# pico.net
KiCad netlist of a schematic drawn in EAGLE
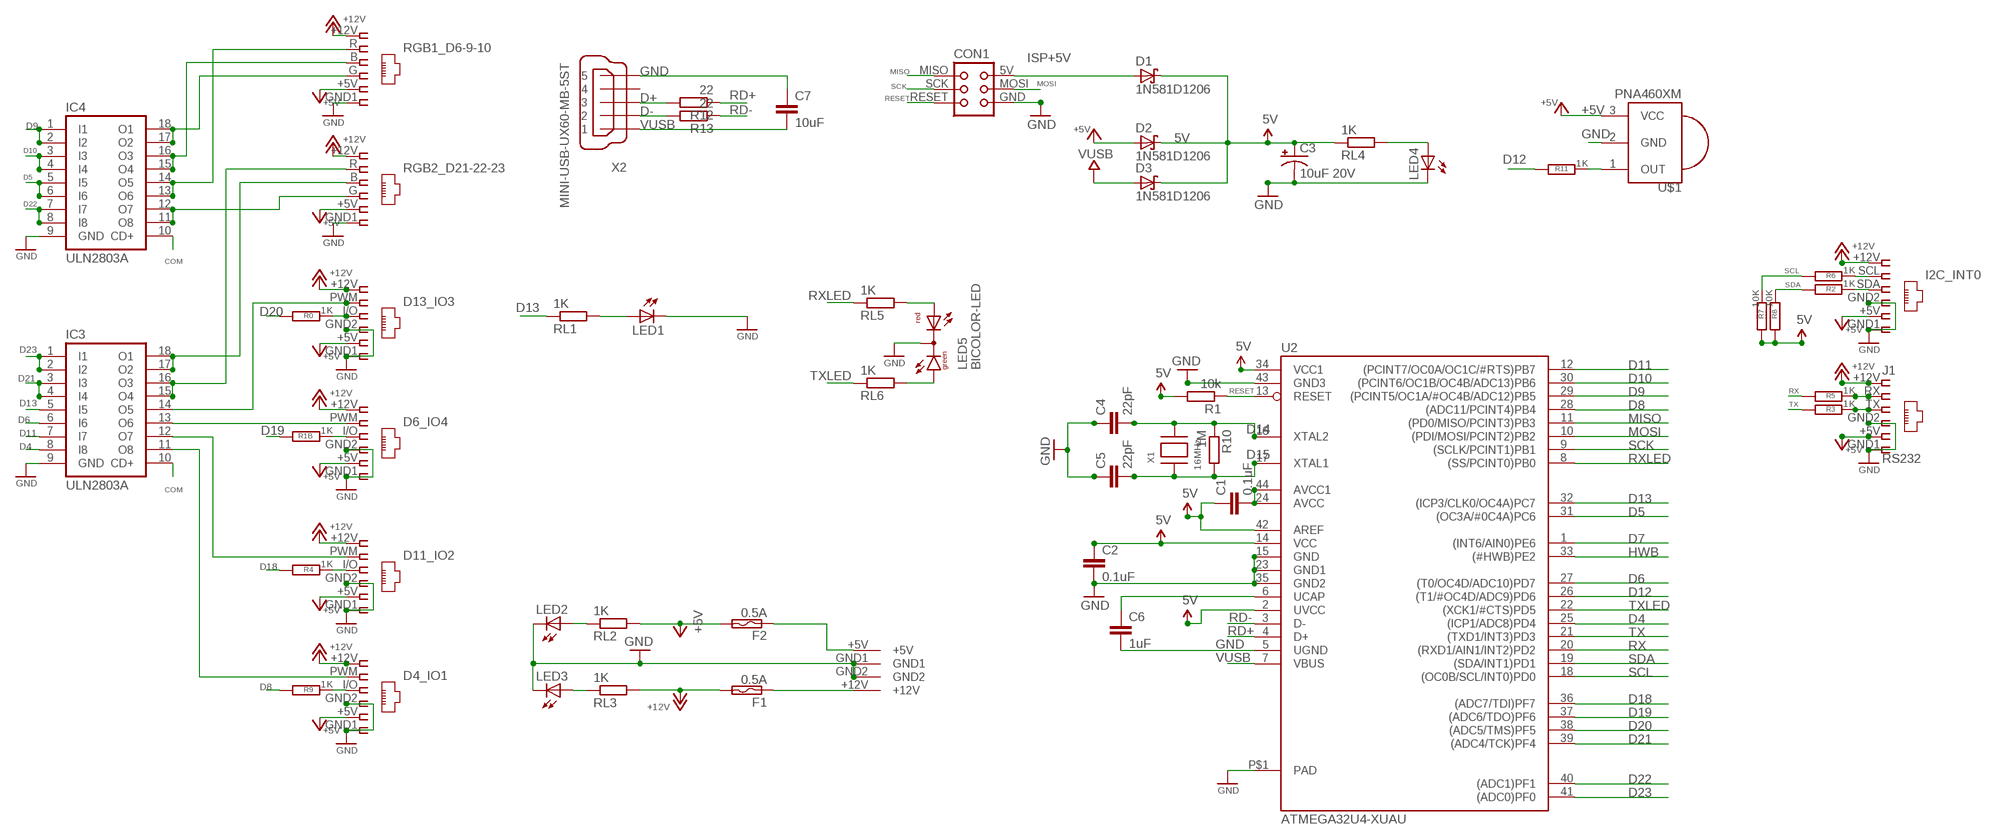
[diagram p0: schematic, sheet 1]

(export (version "E")
  (design (tool "Eeschema 10.0.6"))
  (components
    (comp (ref "C1")
      (value "0.1uF")
      (footprint "eagle-import:C1206")
      (libsource (lib "eagle-import") (part "C-EUC1206"))
    )
    (comp (ref "C2")
      (value "0.1uF")
      (footprint "eagle-import:C1206")
      (libsource (lib "eagle-import") (part "C-EUC1206"))
    )
    (comp (ref "C3")
      (value "10uF 20V")
      (footprint "eagle-import:EIA3216-KIT")
      (libsource (lib "eagle-import") (part "CAP_POL1206-KIT"))
    )
    (comp (ref "C4")
      (value "22pF")
      (footprint "eagle-import:C1206")
      (libsource (lib "eagle-import") (part "C-EUC1206"))
    )
    (comp (ref "C5")
      (value "22pF")
      (footprint "eagle-import:C1206")
      (libsource (lib "eagle-import") (part "C-EUC1206"))
    )
    (comp (ref "C6")
      (value "1uF")
      (footprint "eagle-import:C1206")
      (libsource (lib "eagle-import") (part "C-EUC1206"))
    )
    (comp (ref "C7")
      (value "10uF")
      (footprint "eagle-import:C1206")
      (libsource (lib "eagle-import") (part "C-EUC1206"))
    )
    (comp (ref "CON1")
      (value "TINYISPT")
      (footprint "eagle-import:TC2030-MCP-NL")
      (libsource (lib "eagle-import") (part "TINYISPT"))
    )
    (comp (ref "D1")
      (value "1N581D1206")
      (footprint "eagle-import:LED-1206")
      (libsource (lib "eagle-import") (part "1N581D1206"))
    )
    (comp (ref "D2")
      (value "1N581D1206")
      (footprint "eagle-import:LED-1206")
      (libsource (lib "eagle-import") (part "1N581D1206"))
    )
    (comp (ref "D3")
      (value "1N581D1206")
      (footprint "eagle-import:LED-1206")
      (libsource (lib "eagle-import") (part "1N581D1206"))
    )
    (comp (ref "D4_IO1")
      (value "IO1")
      (footprint "eagle-import:RJ12-STRAIGHT")
      (libsource (lib "eagle-import") (part "RJ12STRAIGHT"))
    )
    (comp (ref "D6_IO4")
      (value "IO3")
      (footprint "eagle-import:RJ12-STRAIGHT")
      (libsource (lib "eagle-import") (part "RJ12STRAIGHT"))
    )
    (comp (ref "D11_IO2")
      (value "IO2")
      (footprint "eagle-import:RJ12-STRAIGHT")
      (libsource (lib "eagle-import") (part "RJ12STRAIGHT"))
    )
    (comp (ref "D13_IO3")
      (value "IO4")
      (footprint "eagle-import:RJ12-STRAIGHT")
      (libsource (lib "eagle-import") (part "RJ12STRAIGHT"))
    )
    (comp (ref "F1")
      (value "0.5A")
      (footprint "eagle-import:C1812")
      (libsource (lib "eagle-import") (part "POLYSWITCHSMD1812"))
    )
    (comp (ref "F2")
      (value "0.5A")
      (footprint "eagle-import:C1812")
      (libsource (lib "eagle-import") (part "POLYSWITCHSMD1812"))
    )
    (comp (ref "I2C_INT0")
      (value "I2C")
      (footprint "eagle-import:RJ12-STRAIGHT-I2C")
      (libsource (lib "eagle-import") (part "RJ12STRAIGHT-I2C"))
    )
    (comp (ref "IC3")
      (value "ULN2803A")
      (footprint "eagle-import:SO18W")
      (libsource (lib "eagle-import") (part "ULN2803A"))
    )
    (comp (ref "IC4")
      (value "ULN2803A")
      (footprint "eagle-import:SO18W")
      (libsource (lib "eagle-import") (part "ULN2803A"))
    )
    (comp (ref "J1")
      (value "RS232")
      (footprint "eagle-import:RJ12-STRAIGHT-RS232")
      (libsource (lib "eagle-import") (part "RJ12STRAIGHT-RS232-SERVER"))
    )
    (comp (ref "LED1")
      (value "LED3MM")
      (footprint "eagle-import:LED3MM")
      (libsource (lib "eagle-import") (part "LED3MM"))
    )
    (comp (ref "LED2")
      (value "5V")
      (footprint "eagle-import:LED3MM")
      (libsource (lib "eagle-import") (part "LED3MM"))
    )
    (comp (ref "LED3")
      (value "12V")
      (footprint "eagle-import:LED3MM")
      (libsource (lib "eagle-import") (part "LED3MM"))
    )
    (comp (ref "LED4")
      (value "5V uC")
      (footprint "eagle-import:LED3MM")
      (libsource (lib "eagle-import") (part "LED3MM"))
    )
    (comp (ref "LED5")
      (value "BICOLOR-LED")
      (footprint "eagle-import:BICOLOR-3MM")
      (libsource (lib "eagle-import") (part "BICOLOR-LED"))
    )
    (comp (ref "R0")
      (value "1K")
      (footprint "eagle-import:M1206")
      (libsource (lib "eagle-import") (part "R-EU_M1206"))
    )
    (comp (ref "R1")
      (value "10k")
      (footprint "eagle-import:M1206")
      (libsource (lib "eagle-import") (part "R-EU_M1206"))
    )
    (comp (ref "R1B")
      (value "1K")
      (footprint "eagle-import:M1206")
      (libsource (lib "eagle-import") (part "R-EU_M1206"))
    )
    (comp (ref "R2")
      (value "1K")
      (footprint "eagle-import:M1206")
      (libsource (lib "eagle-import") (part "R-EU_M1206"))
    )
    (comp (ref "R3")
      (value "1K")
      (footprint "eagle-import:M1206")
      (libsource (lib "eagle-import") (part "R-EU_M1206"))
    )
    (comp (ref "R4")
      (value "1K")
      (footprint "eagle-import:M1206")
      (libsource (lib "eagle-import") (part "R-EU_M1206"))
    )
    (comp (ref "R5")
      (value "1K")
      (footprint "eagle-import:M1206")
      (libsource (lib "eagle-import") (part "R-EU_M1206"))
    )
    (comp (ref "R6")
      (value "1K")
      (footprint "eagle-import:M1206")
      (libsource (lib "eagle-import") (part "R-EU_M1206"))
    )
    (comp (ref "R7")
      (value "10K")
      (footprint "eagle-import:M1206")
      (libsource (lib "eagle-import") (part "R-EU_M1206"))
    )
    (comp (ref "R8")
      (value "10K")
      (footprint "eagle-import:M1206")
      (libsource (lib "eagle-import") (part "R-EU_M1206"))
    )
    (comp (ref "R9")
      (value "1K")
      (footprint "eagle-import:M1206")
      (libsource (lib "eagle-import") (part "R-EU_M1206"))
    )
    (comp (ref "R10")
      (value "1M")
      (footprint "eagle-import:M1206")
      (libsource (lib "eagle-import") (part "R-EU_M1206"))
    )
    (comp (ref "R11")
      (value "1K")
      (footprint "eagle-import:M1206")
      (libsource (lib "eagle-import") (part "R-EU_M1206"))
    )
    (comp (ref "R12")
      (value "22")
      (footprint "eagle-import:M1206")
      (libsource (lib "eagle-import") (part "R-EU_M1206"))
    )
    (comp (ref "R13")
      (value "22")
      (footprint "eagle-import:M1206")
      (libsource (lib "eagle-import") (part "R-EU_M1206"))
    )
    (comp (ref "RGB1_D6-9-10")
      (value "RGB1")
      (footprint "eagle-import:RJ12-STRAIGHT-RGB")
      (libsource (lib "eagle-import") (part "RJ12STRAIGHT-RGB"))
    )
    (comp (ref "RGB2_D21-22-23")
      (value "RGB2")
      (footprint "eagle-import:RJ12-STRAIGHT-RGB")
      (libsource (lib "eagle-import") (part "RJ12STRAIGHT-RGB"))
    )
    (comp (ref "RL1")
      (value "1K")
      (footprint "eagle-import:M1206")
      (libsource (lib "eagle-import") (part "R-EU_M1206"))
    )
    (comp (ref "RL2")
      (value "1K")
      (footprint "eagle-import:M1206")
      (libsource (lib "eagle-import") (part "R-EU_M1206"))
    )
    (comp (ref "RL3")
      (value "1K")
      (footprint "eagle-import:M1206")
      (libsource (lib "eagle-import") (part "R-EU_M1206"))
    )
    (comp (ref "RL4")
      (value "1K")
      (footprint "eagle-import:M1206")
      (libsource (lib "eagle-import") (part "R-EU_M1206"))
    )
    (comp (ref "RL5")
      (value "1K")
      (footprint "eagle-import:M1206")
      (libsource (lib "eagle-import") (part "R-EU_M1206"))
    )
    (comp (ref "RL6")
      (value "1K")
      (footprint "eagle-import:M1206")
      (libsource (lib "eagle-import") (part "R-EU_M1206"))
    )
    (comp (ref "U$1")
      (value "PNA460XM")
      (footprint "eagle-import:PNA460XM")
      (libsource (lib "eagle-import") (part "PNA460XM"))
    )
    (comp (ref "U$2")
      (value "KPJX-4S-S")
      (footprint "eagle-import:KPJX-4S-S")
      (libsource (lib "eagle-import") (part "KPJX-4S-S"))
    )
    (comp (ref "U2")
      (value "ATMEGA32U4-XUAU")
      (footprint "eagle-import:TQFP44-PAD")
      (libsource (lib "eagle-import") (part "ATMEGA32U4-XUAU"))
    )
    (comp (ref "X1")
      (value "16MHz")
      (footprint "eagle-import:NX6035")
      (libsource (lib "eagle-import") (part "XTALNX6035"))
    )
    (comp (ref "X2")
      (value "MINI-USB-UX60-MB-5ST")
      (footprint "eagle-import:UX60-MB-5ST")
      (libsource (lib "eagle-import") (part "MINI-USB-UX60-MB-5ST"))
    )
  )
  (nets
    (net (code "1") (name "+5V") (class "Default")
      (node (ref "D11_IO2") (pin "+5V") (pinfunction "5_+5V") (pintype "bidirectional"))
      (node (ref "D13_IO3") (pin "+5V") (pinfunction "5_+5V") (pintype "bidirectional"))
      (node (ref "D2") (pin "A") (pinfunction "A_A") (pintype "passive"))
      (node (ref "D4_IO1") (pin "+5V") (pinfunction "5_+5V") (pintype "bidirectional"))
      (node (ref "D6_IO4") (pin "+5V") (pinfunction "5_+5V") (pintype "bidirectional"))
      (node (ref "F2") (pin "2") (pinfunction "2_2") (pintype "passive"))
      (node (ref "I2C_INT0") (pin "+5V") (pinfunction "5_+5V") (pintype "bidirectional"))
      (node (ref "J1") (pin "+5V") (pinfunction "5_+5V") (pintype "bidirectional"))
      (node (ref "RGB1_D6-9-10") (pin "+5V") (pinfunction "5_+5V") (pintype "bidirectional"))
      (node (ref "RGB2_D21-22-23") (pin "+5V") (pinfunction "5_+5V") (pintype "bidirectional"))
      (node (ref "RL2") (pin "2") (pinfunction "2_2") (pintype "passive"))
      (node (ref "U$1") (pin "3") (pinfunction "VCC_3") (pintype "power_in"))
    )
    (net (code "2") (name "+12V") (class "Default")
      (node (ref "D11_IO2") (pin "+12V") (pinfunction "1_+12V") (pintype "bidirectional"))
      (node (ref "D13_IO3") (pin "+12V") (pinfunction "1_+12V") (pintype "bidirectional"))
      (node (ref "D4_IO1") (pin "+12V") (pinfunction "1_+12V") (pintype "bidirectional"))
      (node (ref "D6_IO4") (pin "+12V") (pinfunction "1_+12V") (pintype "bidirectional"))
      (node (ref "F1") (pin "2") (pinfunction "2_2") (pintype "passive"))
      (node (ref "I2C_INT0") (pin "+12V") (pinfunction "1_+12V") (pintype "bidirectional"))
      (node (ref "J1") (pin "+12V") (pinfunction "1_+12V") (pintype "bidirectional"))
      (node (ref "RGB1_D6-9-10") (pin "+12V") (pinfunction "1_+12V") (pintype "bidirectional"))
      (node (ref "RGB2_D21-22-23") (pin "+12V") (pinfunction "1_+12V") (pintype "bidirectional"))
      (node (ref "RL3") (pin "2") (pinfunction "2_2") (pintype "passive"))
    )
    (net (code "3") (name "/COM") (class "Default")
      (node (ref "IC3") (pin "10") (pinfunction "CD+_10") (pintype "passive"))
      (node (ref "IC4") (pin "10") (pinfunction "CD+_10") (pintype "passive"))
    )
    (net (code "4") (name "/D+") (class "Default")
      (node (ref "R12") (pin "2") (pinfunction "2_2") (pintype "passive"))
      (node (ref "X2") (pin "3") (pinfunction "3_3") (pintype "input"))
    )
    (net (code "5") (name "/D-") (class "Default")
      (node (ref "R13") (pin "2") (pinfunction "2_2") (pintype "passive"))
      (node (ref "X2") (pin "2") (pinfunction "2_2") (pintype "input"))
    )
    (net (code "6") (name "/D4") (class "Default")
      (node (ref "IC3") (pin "8") (pinfunction "I8_8") (pintype "input"))
      (node (ref "U2") (pin "25") (pinfunction "(ICP1/ADC8)PD4_25") (pintype "bidirectional"))
    )
    (net (code "7") (name "/D5") (class "Default")
      (node (ref "IC4") (pin "5") (pinfunction "I5_5") (pintype "input"))
      (node (ref "IC4") (pin "6") (pinfunction "I6_6") (pintype "input"))
      (node (ref "U2") (pin "31") (pinfunction "(OC3A/#0C4A)PC6_31") (pintype "bidirectional"))
    )
    (net (code "8") (name "/D6") (class "Default")
      (node (ref "IC3") (pin "6") (pinfunction "I6_6") (pintype "input"))
      (node (ref "U2") (pin "27") (pinfunction "(T0/OC4D/ADC10)PD7_27") (pintype "bidirectional"))
    )
    (net (code "9") (name "/D7") (class "Default")
      (node (ref "U2") (pin "1") (pinfunction "(INT6/AIN0)PE6_1") (pintype "bidirectional"))
    )
    (net (code "10") (name "/D8") (class "Default")
      (node (ref "R9") (pin "2") (pinfunction "2_2") (pintype "passive"))
      (node (ref "U2") (pin "28") (pinfunction "(ADC11/PCINT4)PB4_28") (pintype "bidirectional"))
    )
    (net (code "11") (name "/D9") (class "Default")
      (node (ref "IC4") (pin "1") (pinfunction "I1_1") (pintype "input"))
      (node (ref "IC4") (pin "2") (pinfunction "I2_2") (pintype "input"))
      (node (ref "U2") (pin "29") (pinfunction "(PCINT5/OC1A/#OC4B/ADC12)PB5_29") (pintype "bidirectional"))
    )
    (net (code "12") (name "/D10") (class "Default")
      (node (ref "IC4") (pin "3") (pinfunction "I3_3") (pintype "input"))
      (node (ref "IC4") (pin "4") (pinfunction "I4_4") (pintype "input"))
      (node (ref "U2") (pin "30") (pinfunction "(PCINT6/OC1B/OC4B/ADC13)PB6_30") (pintype "bidirectional"))
    )
    (net (code "13") (name "/D11") (class "Default")
      (node (ref "IC3") (pin "7") (pinfunction "I7_7") (pintype "input"))
      (node (ref "U2") (pin "12") (pinfunction "(PCINT7/OC0A/OC1C/#RTS)PB7_12") (pintype "bidirectional"))
    )
    (net (code "14") (name "/D12") (class "Default")
      (node (ref "R11") (pin "2") (pinfunction "2_2") (pintype "passive"))
      (node (ref "U2") (pin "26") (pinfunction "(T1/#OC4D/ADC9)PD6_26") (pintype "bidirectional"))
    )
    (net (code "15") (name "/D13") (class "Default")
      (node (ref "IC3") (pin "5") (pinfunction "I5_5") (pintype "input"))
      (node (ref "RL1") (pin "1") (pinfunction "1_1") (pintype "passive"))
      (node (ref "U2") (pin "32") (pinfunction "(ICP3/CLK0/OC4A)PC7_32") (pintype "bidirectional"))
    )
    (net (code "16") (name "/D14") (class "Default")
      (node (ref "C4") (pin "2") (pinfunction "2_2") (pintype "passive"))
      (node (ref "R10") (pin "1") (pinfunction "1_1") (pintype "passive"))
      (node (ref "U2") (pin "16") (pinfunction "XTAL2_16") (pintype "bidirectional"))
      (node (ref "X1") (pin "P$2") (pinfunction "P$2_P$2") (pintype "bidirectional"))
    )
    (net (code "17") (name "/D15") (class "Default")
      (node (ref "C5") (pin "2") (pinfunction "2_2") (pintype "passive"))
      (node (ref "R10") (pin "2") (pinfunction "2_2") (pintype "passive"))
      (node (ref "U2") (pin "17") (pinfunction "XTAL1_17") (pintype "bidirectional"))
      (node (ref "X1") (pin "P$1") (pinfunction "P$1_P$1") (pintype "bidirectional"))
    )
    (net (code "18") (name "/D18") (class "Default")
      (node (ref "R4") (pin "2") (pinfunction "2_2") (pintype "passive"))
      (node (ref "U2") (pin "36") (pinfunction "(ADC7/TDI)PF7_36") (pintype "bidirectional"))
    )
    (net (code "19") (name "/D19") (class "Default")
      (node (ref "R1B") (pin "2") (pinfunction "2_2") (pintype "passive"))
      (node (ref "U2") (pin "37") (pinfunction "(ADC6/TDO)PF6_37") (pintype "bidirectional"))
    )
    (net (code "20") (name "/D20") (class "Default")
      (node (ref "R0") (pin "2") (pinfunction "2_2") (pintype "passive"))
      (node (ref "U2") (pin "38") (pinfunction "(ADC5/TMS)PF5_38") (pintype "bidirectional"))
    )
    (net (code "21") (name "/D21") (class "Default")
      (node (ref "IC3") (pin "3") (pinfunction "I3_3") (pintype "input"))
      (node (ref "IC3") (pin "4") (pinfunction "I4_4") (pintype "input"))
      (node (ref "U2") (pin "39") (pinfunction "(ADC4/TCK)PF4_39") (pintype "bidirectional"))
    )
    (net (code "22") (name "/D22") (class "Default")
      (node (ref "IC4") (pin "7") (pinfunction "I7_7") (pintype "input"))
      (node (ref "IC4") (pin "8") (pinfunction "I8_8") (pintype "input"))
      (node (ref "U2") (pin "40") (pinfunction "(ADC1)PF1_40") (pintype "bidirectional"))
    )
    (net (code "23") (name "/D23") (class "Default")
      (node (ref "IC3") (pin "1") (pinfunction "I1_1") (pintype "input"))
      (node (ref "IC3") (pin "2") (pinfunction "I2_2") (pintype "input"))
      (node (ref "U2") (pin "41") (pinfunction "(ADC0)PF0_41") (pintype "bidirectional"))
    )
    (net (code "24") (name "/HWB") (class "Default")
      (node (ref "U2") (pin "33") (pinfunction "(#HWB)PE2_33") (pintype "bidirectional"))
    )
    (net (code "25") (name "/ISP+5V") (class "Default")
      (node (ref "CON1") (pin "5V") (pinfunction "VCC_5V") (pintype "passive"))
      (node (ref "D1") (pin "A") (pinfunction "A_A") (pintype "passive"))
    )
    (net (code "26") (name "/MISO") (class "Default")
      (node (ref "CON1") (pin "MISO") (pinfunction "MISO_MISO") (pintype "passive"))
      (node (ref "U2") (pin "11") (pinfunction "(PD0/MISO/PCINT3)PB3_11") (pintype "bidirectional"))
    )
    (net (code "27") (name "/MOSI") (class "Default")
      (node (ref "CON1") (pin "MOSI") (pinfunction "MOSI_MOSI") (pintype "passive"))
      (node (ref "U2") (pin "10") (pinfunction "(PDI/MOSI/PCINT2)PB2_10") (pintype "bidirectional"))
    )
    (net (code "28") (name "/RD+") (class "Default")
      (node (ref "R12") (pin "1") (pinfunction "1_1") (pintype "passive"))
      (node (ref "U2") (pin "4") (pinfunction "D+_4") (pintype "bidirectional"))
    )
    (net (code "29") (name "/RD-") (class "Default")
      (node (ref "R13") (pin "1") (pinfunction "1_1") (pintype "passive"))
      (node (ref "U2") (pin "3") (pinfunction "D-_3") (pintype "bidirectional"))
    )
    (net (code "30") (name "/RESET") (class "Default")
      (node (ref "CON1") (pin "RESET") (pinfunction "RESET_RESET") (pintype "passive"))
      (node (ref "R1") (pin "1") (pinfunction "1_1") (pintype "passive"))
      (node (ref "U2") (pin "13") (pinfunction "RESET_13") (pintype "input"))
    )
    (net (code "31") (name "/RX") (class "Default")
      (node (ref "R5") (pin "2") (pinfunction "2_2") (pintype "passive"))
      (node (ref "U2") (pin "20") (pinfunction "(RXD1/AIN1/INT2)PD2_20") (pintype "bidirectional"))
    )
    (net (code "32") (name "/RXLED") (class "Default")
      (node (ref "RL5") (pin "1") (pinfunction "1_1") (pintype "passive"))
      (node (ref "U2") (pin "8") (pinfunction "(SS/PCINT0)PB0_8") (pintype "bidirectional"))
    )
    (net (code "33") (name "/SCK") (class "Default")
      (node (ref "CON1") (pin "SCK") (pinfunction "SCK_SCK") (pintype "passive"))
      (node (ref "U2") (pin "9") (pinfunction "(SCLK/PCINT1)PB1_9") (pintype "bidirectional"))
    )
    (net (code "34") (name "/SCL") (class "Default")
      (node (ref "R6") (pin "2") (pinfunction "2_2") (pintype "passive"))
      (node (ref "R7") (pin "1") (pinfunction "1_1") (pintype "passive"))
      (node (ref "U2") (pin "18") (pinfunction "(OC0B/SCL/INT0)PD0_18") (pintype "bidirectional"))
    )
    (net (code "35") (name "/SDA") (class "Default")
      (node (ref "R2") (pin "2") (pinfunction "2_2") (pintype "passive"))
      (node (ref "R8") (pin "1") (pinfunction "1_1") (pintype "passive"))
      (node (ref "U2") (pin "19") (pinfunction "(SDA/INT1)PD1_19") (pintype "bidirectional"))
    )
    (net (code "36") (name "/TX") (class "Default")
      (node (ref "R3") (pin "2") (pinfunction "2_2") (pintype "passive"))
      (node (ref "U2") (pin "21") (pinfunction "(TXD1/INT3)PD3_21") (pintype "bidirectional"))
    )
    (net (code "37") (name "/TXLED") (class "Default")
      (node (ref "RL6") (pin "1") (pinfunction "1_1") (pintype "passive"))
      (node (ref "U2") (pin "22") (pinfunction "(XCK1/#CTS)PD5_22") (pintype "bidirectional"))
    )
    (net (code "38") (name "5V") (class "Default")
      (node (ref "C1") (pin "1") (pinfunction "1_1") (pintype "passive"))
      (node (ref "C2") (pin "1") (pinfunction "1_1") (pintype "passive"))
      (node (ref "C3") (pin "A") (pinfunction "+_A") (pintype "passive"))
      (node (ref "D1") (pin "C") (pinfunction "C_C") (pintype "passive"))
      (node (ref "D2") (pin "C") (pinfunction "C_C") (pintype "passive"))
      (node (ref "D3") (pin "C") (pinfunction "C_C") (pintype "passive"))
      (node (ref "R1") (pin "2") (pinfunction "2_2") (pintype "passive"))
      (node (ref "R7") (pin "2") (pinfunction "2_2") (pintype "passive"))
      (node (ref "R8") (pin "2") (pinfunction "2_2") (pintype "passive"))
      (node (ref "RL4") (pin "1") (pinfunction "1_1") (pintype "passive"))
      (node (ref "U2") (pin "14") (pinfunction "VCC_14") (pintype "power_in"))
      (node (ref "U2") (pin "2") (pinfunction "UVCC_2") (pintype "power_in"))
      (node (ref "U2") (pin "34") (pinfunction "VCC1_34") (pintype "power_in"))
      (node (ref "U2") (pin "42") (pinfunction "AREF_42") (pintype "power_in"))
    )
    (net (code "39") (name "GND") (class "Default")
      (node (ref "C2") (pin "2") (pinfunction "2_2") (pintype "passive"))
      (node (ref "C3") (pin "C") (pinfunction "-_C") (pintype "passive"))
      (node (ref "C4") (pin "1") (pinfunction "1_1") (pintype "passive"))
      (node (ref "C5") (pin "1") (pinfunction "1_1") (pintype "passive"))
      (node (ref "C6") (pin "2") (pinfunction "2_2") (pintype "passive"))
      (node (ref "C7") (pin "1") (pinfunction "1_1") (pintype "passive"))
      (node (ref "CON1") (pin "GND") (pinfunction "GND_GND") (pintype "passive"))
      (node (ref "D11_IO2") (pin "GND1") (pinfunction "6_GND1") (pintype "bidirectional"))
      (node (ref "D11_IO2") (pin "GND2") (pinfunction "4_GND2") (pintype "bidirectional"))
      (node (ref "D13_IO3") (pin "GND1") (pinfunction "6_GND1") (pintype "bidirectional"))
      (node (ref "D13_IO3") (pin "GND2") (pinfunction "4_GND2") (pintype "bidirectional"))
      (node (ref "D4_IO1") (pin "GND1") (pinfunction "6_GND1") (pintype "bidirectional"))
      (node (ref "D4_IO1") (pin "GND2") (pinfunction "4_GND2") (pintype "bidirectional"))
      (node (ref "D6_IO4") (pin "GND1") (pinfunction "6_GND1") (pintype "bidirectional"))
      (node (ref "D6_IO4") (pin "GND2") (pinfunction "4_GND2") (pintype "bidirectional"))
      (node (ref "I2C_INT0") (pin "GND1") (pinfunction "6_GND1") (pintype "bidirectional"))
      (node (ref "I2C_INT0") (pin "GND2") (pinfunction "4_GND2") (pintype "bidirectional"))
      (node (ref "IC3") (pin "9") (pinfunction "GND_9") (pintype "power_in"))
      (node (ref "IC4") (pin "9") (pinfunction "GND_9") (pintype "power_in"))
      (node (ref "J1") (pin "GND1") (pinfunction "6_GND1") (pintype "bidirectional"))
      (node (ref "J1") (pin "GND2") (pinfunction "4_GND2") (pintype "bidirectional"))
      (node (ref "LED1") (pin "K") (pinfunction "C_K") (pintype "passive"))
      (node (ref "LED2") (pin "K") (pinfunction "C_K") (pintype "passive"))
      (node (ref "LED3") (pin "K") (pinfunction "C_K") (pintype "passive"))
      (node (ref "LED4") (pin "K") (pinfunction "C_K") (pintype "passive"))
      (node (ref "LED5") (pin "2") (pinfunction "C_2") (pintype "passive"))
      (node (ref "RGB1_D6-9-10") (pin "GND1") (pinfunction "6_GND1") (pintype "bidirectional"))
      (node (ref "RGB2_D21-22-23") (pin "GND1") (pinfunction "6_GND1") (pintype "bidirectional"))
      (node (ref "U$1") (pin "2") (pinfunction "GND_2") (pintype "power_in"))
      (node (ref "U$2") (pin "GND1") (pinfunction "GND1_GND1") (pintype "input"))
      (node (ref "U$2") (pin "GND2") (pinfunction "GND2_GND2") (pintype "input"))
      (node (ref "U2") (pin "15") (pinfunction "GND_15") (pintype "power_in"))
      (node (ref "U2") (pin "23") (pinfunction "GND1_23") (pintype "power_in"))
      (node (ref "U2") (pin "35") (pinfunction "GND2_35") (pintype "power_in"))
      (node (ref "U2") (pin "43") (pinfunction "GND3_43") (pintype "power_in"))
      (node (ref "U2") (pin "5") (pinfunction "UGND_5") (pintype "power_in"))
      (node (ref "U2") (pin "P$1") (pinfunction "PAD_P$1") (pintype "power_in"))
      (node (ref "X2") (pin "5") (pinfunction "5_5") (pintype "input"))
    )
    (net (code "40") (name "Net-(D4_IO1-2)") (class "Default")
      (node (ref "D4_IO1") (pin "PWM") (pinfunction "2_PWM") (pintype "bidirectional"))
      (node (ref "IC3") (pin "11") (pinfunction "O8_11") (pintype "open_collector"))
    )
    (net (code "41") (name "Net-(D4_IO1-3)") (class "Default")
      (node (ref "D4_IO1") (pin "I/O") (pinfunction "3_I/O") (pintype "bidirectional"))
      (node (ref "R9") (pin "1") (pinfunction "1_1") (pintype "passive"))
    )
    (net (code "42") (name "Net-(D6_IO4-2)") (class "Default")
      (node (ref "D6_IO4") (pin "PWM") (pinfunction "2_PWM") (pintype "bidirectional"))
      (node (ref "IC3") (pin "13") (pinfunction "O6_13") (pintype "open_collector"))
    )
    (net (code "43") (name "Net-(D6_IO4-3)") (class "Default")
      (node (ref "D6_IO4") (pin "I/O") (pinfunction "3_I/O") (pintype "bidirectional"))
      (node (ref "R1B") (pin "1") (pinfunction "1_1") (pintype "passive"))
    )
    (net (code "44") (name "Net-(D11_IO2-2)") (class "Default")
      (node (ref "D11_IO2") (pin "PWM") (pinfunction "2_PWM") (pintype "bidirectional"))
      (node (ref "IC3") (pin "12") (pinfunction "O7_12") (pintype "open_collector"))
    )
    (net (code "45") (name "Net-(D11_IO2-3)") (class "Default")
      (node (ref "D11_IO2") (pin "I/O") (pinfunction "3_I/O") (pintype "bidirectional"))
      (node (ref "R4") (pin "1") (pinfunction "1_1") (pintype "passive"))
    )
    (net (code "46") (name "Net-(D13_IO3-2)") (class "Default")
      (node (ref "D13_IO3") (pin "PWM") (pinfunction "2_PWM") (pintype "bidirectional"))
      (node (ref "IC3") (pin "14") (pinfunction "O5_14") (pintype "open_collector"))
    )
    (net (code "47") (name "Net-(D13_IO3-3)") (class "Default")
      (node (ref "D13_IO3") (pin "I/O") (pinfunction "3_I/O") (pintype "bidirectional"))
      (node (ref "R0") (pin "1") (pinfunction "1_1") (pintype "passive"))
    )
    (net (code "48") (name "Net-(F1-Pad1)") (class "Default")
      (node (ref "F1") (pin "1") (pinfunction "1_1") (pintype "passive"))
      (node (ref "U$2") (pin "+12V") (pinfunction "+12V_+12V") (pintype "power_in"))
    )
    (net (code "49") (name "Net-(F2-Pad1)") (class "Default")
      (node (ref "F2") (pin "1") (pinfunction "1_1") (pintype "passive"))
      (node (ref "U$2") (pin "+5V") (pinfunction "+5V_+5V") (pintype "power_in"))
    )
    (net (code "50") (name "Net-(I2C_INT0-2)") (class "Default")
      (node (ref "I2C_INT0") (pin "SCL") (pinfunction "2_SCL") (pintype "bidirectional"))
      (node (ref "R6") (pin "1") (pinfunction "1_1") (pintype "passive"))
    )
    (net (code "51") (name "Net-(I2C_INT0-3)") (class "Default")
      (node (ref "I2C_INT0") (pin "SDA") (pinfunction "3_SDA") (pintype "bidirectional"))
      (node (ref "R2") (pin "1") (pinfunction "1_1") (pintype "passive"))
    )
    (net (code "52") (name "Net-(IC3-O1)") (class "Default")
      (node (ref "IC3") (pin "17") (pinfunction "O2_17") (pintype "open_collector"))
      (node (ref "IC3") (pin "18") (pinfunction "O1_18") (pintype "open_collector"))
      (node (ref "RGB2_D21-22-23") (pin "B") (pinfunction "3_B") (pintype "bidirectional"))
    )
    (net (code "53") (name "Net-(IC3-O3)") (class "Default")
      (node (ref "IC3") (pin "15") (pinfunction "O4_15") (pintype "open_collector"))
      (node (ref "IC3") (pin "16") (pinfunction "O3_16") (pintype "open_collector"))
      (node (ref "RGB2_D21-22-23") (pin "R") (pinfunction "2_R") (pintype "bidirectional"))
    )
    (net (code "54") (name "Net-(IC4-O1)") (class "Default")
      (node (ref "IC4") (pin "17") (pinfunction "O2_17") (pintype "open_collector"))
      (node (ref "IC4") (pin "18") (pinfunction "O1_18") (pintype "open_collector"))
      (node (ref "RGB1_D6-9-10") (pin "G") (pinfunction "4_G") (pintype "bidirectional"))
    )
    (net (code "55") (name "Net-(IC4-O3)") (class "Default")
      (node (ref "IC4") (pin "15") (pinfunction "O4_15") (pintype "open_collector"))
      (node (ref "IC4") (pin "16") (pinfunction "O3_16") (pintype "open_collector"))
      (node (ref "RGB1_D6-9-10") (pin "B") (pinfunction "3_B") (pintype "bidirectional"))
    )
    (net (code "56") (name "Net-(IC4-O5)") (class "Default")
      (node (ref "IC4") (pin "13") (pinfunction "O6_13") (pintype "open_collector"))
      (node (ref "IC4") (pin "14") (pinfunction "O5_14") (pintype "open_collector"))
      (node (ref "RGB1_D6-9-10") (pin "R") (pinfunction "2_R") (pintype "bidirectional"))
    )
    (net (code "57") (name "Net-(IC4-O7)") (class "Default")
      (node (ref "IC4") (pin "11") (pinfunction "O8_11") (pintype "open_collector"))
      (node (ref "IC4") (pin "12") (pinfunction "O7_12") (pintype "open_collector"))
      (node (ref "RGB2_D21-22-23") (pin "G") (pinfunction "4_G") (pintype "bidirectional"))
    )
    (net (code "58") (name "Net-(J1-2)") (class "Default")
      (node (ref "J1") (pin "RX") (pinfunction "2_RX") (pintype "bidirectional"))
      (node (ref "R5") (pin "1") (pinfunction "1_1") (pintype "passive"))
    )
    (net (code "59") (name "Net-(J1-3)") (class "Default")
      (node (ref "J1") (pin "TX") (pinfunction "3_TX") (pintype "bidirectional"))
      (node (ref "R3") (pin "1") (pinfunction "1_1") (pintype "passive"))
    )
    (net (code "60") (name "Net-(LED1-PadA)") (class "Default")
      (node (ref "LED1") (pin "A") (pinfunction "A_A") (pintype "passive"))
      (node (ref "RL1") (pin "2") (pinfunction "2_2") (pintype "passive"))
    )
    (net (code "61") (name "Net-(LED2-PadA)") (class "Default")
      (node (ref "LED2") (pin "A") (pinfunction "A_A") (pintype "passive"))
      (node (ref "RL2") (pin "1") (pinfunction "1_1") (pintype "passive"))
    )
    (net (code "62") (name "Net-(LED3-PadA)") (class "Default")
      (node (ref "LED3") (pin "A") (pinfunction "A_A") (pintype "passive"))
      (node (ref "RL3") (pin "1") (pinfunction "1_1") (pintype "passive"))
    )
    (net (code "63") (name "Net-(LED4-PadA)") (class "Default")
      (node (ref "LED4") (pin "A") (pinfunction "A_A") (pintype "passive"))
      (node (ref "RL4") (pin "2") (pinfunction "2_2") (pintype "passive"))
    )
    (net (code "64") (name "Net-(LED5-AG)") (class "Default")
      (node (ref "LED5") (pin "1") (pinfunction "AG_1") (pintype "passive"))
      (node (ref "RL6") (pin "2") (pinfunction "2_2") (pintype "passive"))
    )
    (net (code "65") (name "Net-(LED5-AR)") (class "Default")
      (node (ref "LED5") (pin "3") (pinfunction "AR_3") (pintype "passive"))
      (node (ref "RL5") (pin "2") (pinfunction "2_2") (pintype "passive"))
    )
    (net (code "66") (name "Net-(U$1-OUT)") (class "Default")
      (node (ref "R11") (pin "1") (pinfunction "1_1") (pintype "passive"))
      (node (ref "U$1") (pin "1") (pinfunction "OUT_1") (pintype "output"))
    )
    (net (code "67") (name "Net-(U2-AVCC)") (class "Default")
      (node (ref "C1") (pin "2") (pinfunction "2_2") (pintype "passive"))
      (node (ref "U2") (pin "24") (pinfunction "AVCC_24") (pintype "power_in"))
      (node (ref "U2") (pin "44") (pinfunction "AVCC1_44") (pintype "power_in"))
    )
    (net (code "68") (name "Net-(U2-UCAP)") (class "Default")
      (node (ref "C6") (pin "1") (pinfunction "1_1") (pintype "passive"))
      (node (ref "U2") (pin "6") (pinfunction "UCAP_6") (pintype "passive"))
    )
    (net (code "69") (name "VUSB") (class "Default")
      (node (ref "C7") (pin "2") (pinfunction "2_2") (pintype "passive"))
      (node (ref "D3") (pin "A") (pinfunction "A_A") (pintype "passive"))
      (node (ref "U2") (pin "7") (pinfunction "VBUS_7") (pintype "input"))
      (node (ref "X2") (pin "1") (pinfunction "1_1") (pintype "input"))
    )
    (net (code "70") (name "unconnected-(X2-Pad4)") (class "Default")
      (node (ref "X2") (pin "4") (pinfunction "4_4") (pintype "input"))
    )
  )
)
